# schematic.net
KiCad netlist of a schematic drawn in EAGLE
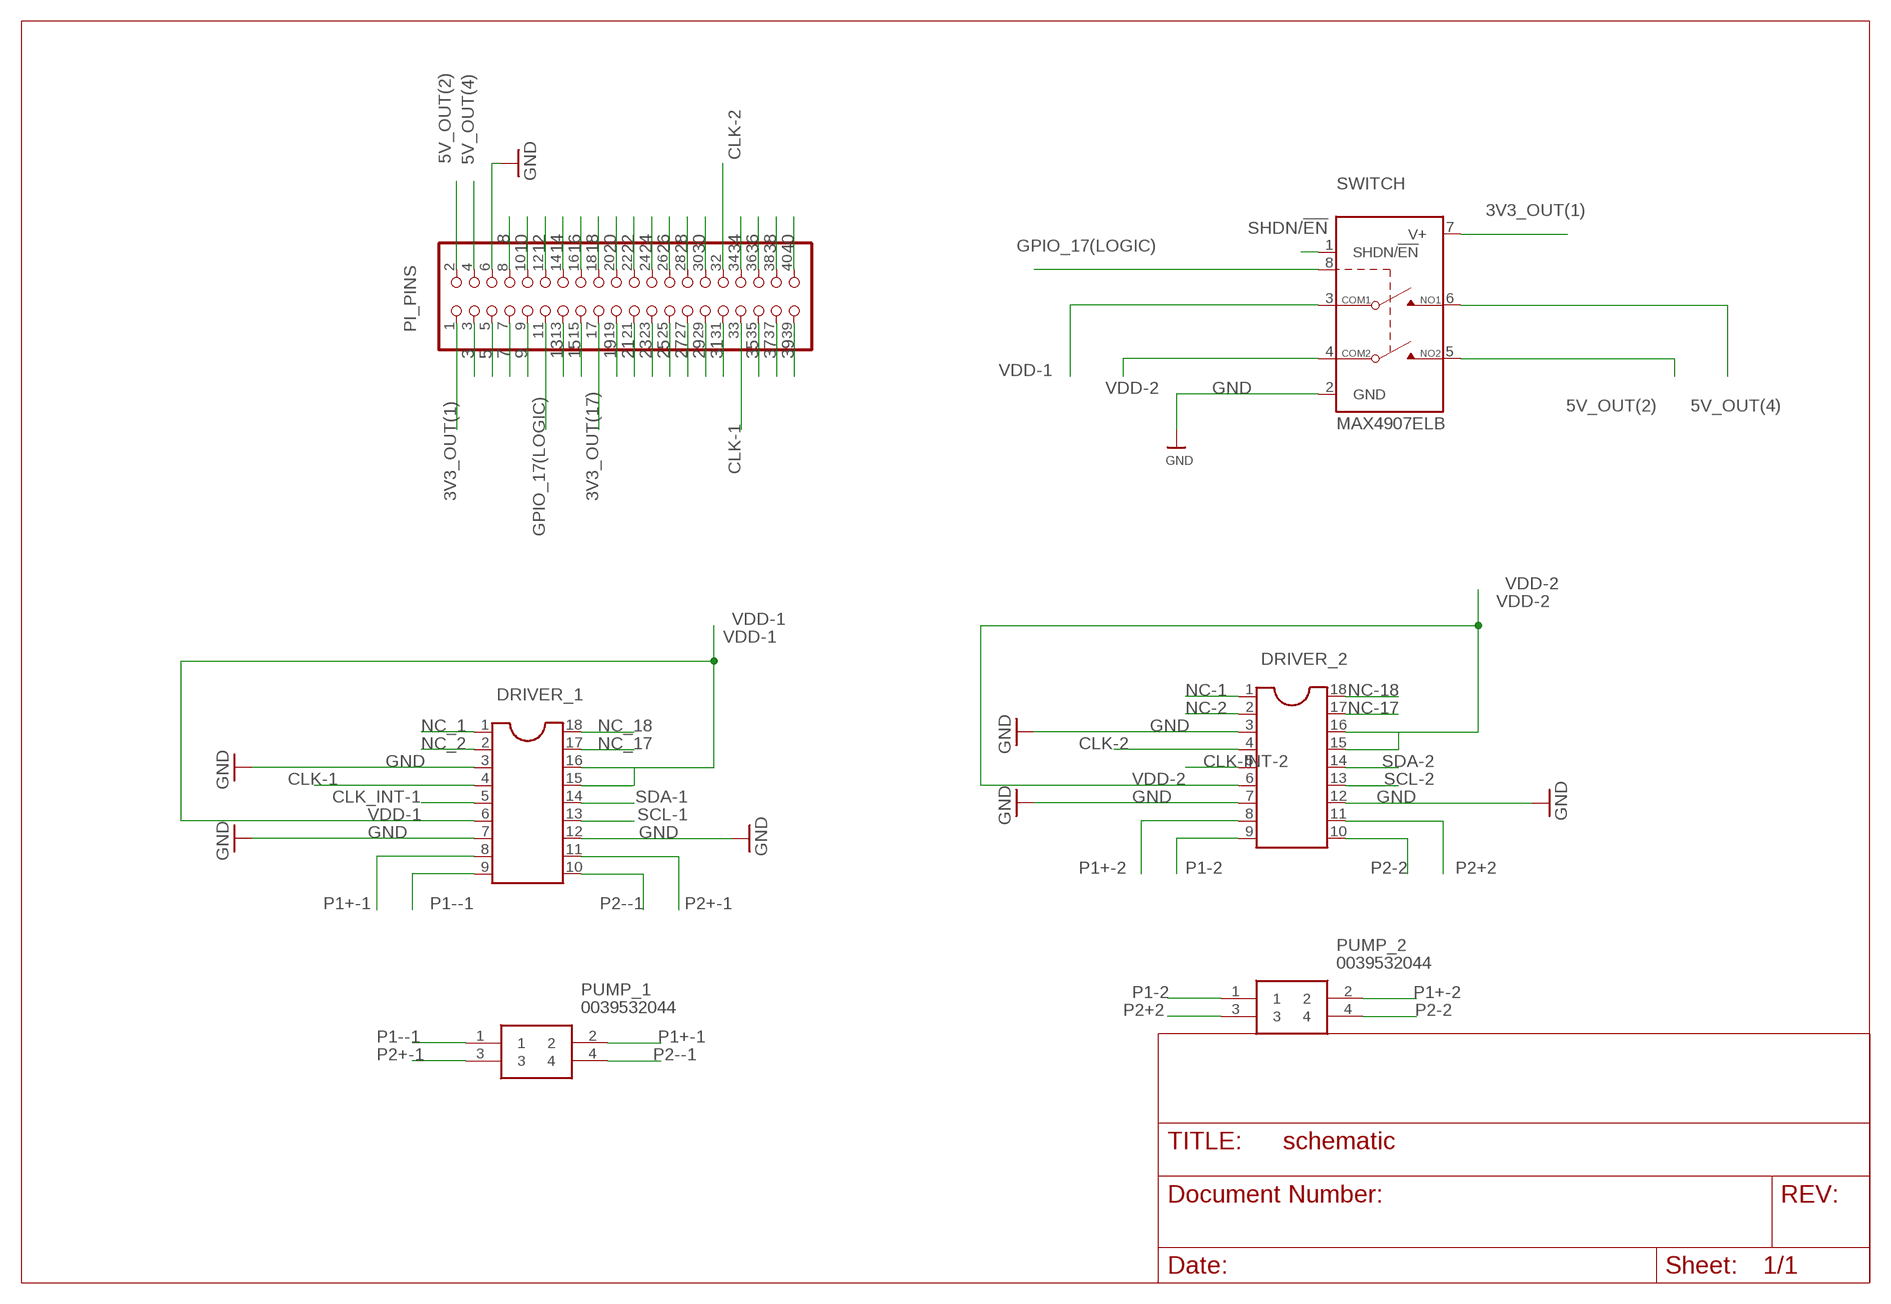
[diagram p0: schematic, sheet 1]

(export (version "E")
  (design (tool "Eeschema 10.0.6"))
  (components
    (comp (ref "DRIVER_1")
      (value "DIL18")
      (footprint "eagle-import:DIL18")
      (libsource (lib "eagle-import") (part "DIL18"))
    )
    (comp (ref "DRIVER_2")
      (value "DIL18")
      (footprint "eagle-import:DIL18")
      (libsource (lib "eagle-import") (part "DIL18"))
    )
    (comp (ref "PI_PINS")
      (value "PINHD-2X20")
      (footprint "eagle-import:2X20")
      (libsource (lib "eagle-import") (part "PINHD-2X20"))
    )
    (comp (ref "PUMP_1")
      (value "0039532044")
      (footprint "eagle-import:0039532044")
      (libsource (lib "eagle-import") (part "0039532044"))
    )
    (comp (ref "PUMP_2")
      (value "0039532044")
      (footprint "eagle-import:0039532044")
      (libsource (lib "eagle-import") (part "0039532044"))
    )
    (comp (ref "SWITCH")
      (value "MAX4907ELB")
      (footprint "eagle-import:UDFN8")
      (libsource (lib "eagle-import") (part "MAX4907ELB"))
    )
  )
  (nets
    (net (code "1") (name "/3") (class "Default")
      (node (ref "PI_PINS") (pin "3") (pinfunction "3_3") (pintype "passive"))
    )
    (net (code "2") (name "/3V3_OUT(1)") (class "Default")
      (node (ref "PI_PINS") (pin "1") (pinfunction "1_1") (pintype "passive"))
      (node (ref "SWITCH") (pin "7") (pinfunction "V+_7") (pintype "input"))
    )
    (net (code "3") (name "/3V3_OUT(17)") (class "Default")
      (node (ref "PI_PINS") (pin "17") (pinfunction "17_17") (pintype "passive"))
    )
    (net (code "4") (name "/5") (class "Default")
      (node (ref "PI_PINS") (pin "5") (pinfunction "5_5") (pintype "passive"))
    )
    (net (code "5") (name "/5V_OUT(2)") (class "Default")
      (node (ref "PI_PINS") (pin "2") (pinfunction "2_2") (pintype "passive"))
      (node (ref "SWITCH") (pin "5") (pinfunction "NO2_5") (pintype "bidirectional"))
    )
    (net (code "6") (name "/5V_OUT(4)") (class "Default")
      (node (ref "PI_PINS") (pin "4") (pinfunction "4_4") (pintype "passive"))
      (node (ref "SWITCH") (pin "6") (pinfunction "NO1_6") (pintype "bidirectional"))
    )
    (net (code "7") (name "/7") (class "Default")
      (node (ref "PI_PINS") (pin "7") (pinfunction "7_7") (pintype "passive"))
    )
    (net (code "8") (name "/8") (class "Default")
      (node (ref "PI_PINS") (pin "8") (pinfunction "8_8") (pintype "passive"))
    )
    (net (code "9") (name "/9") (class "Default")
      (node (ref "PI_PINS") (pin "9") (pinfunction "9_9") (pintype "passive"))
    )
    (net (code "10") (name "/10") (class "Default")
      (node (ref "PI_PINS") (pin "10") (pinfunction "10_10") (pintype "passive"))
    )
    (net (code "11") (name "/12") (class "Default")
      (node (ref "PI_PINS") (pin "12") (pinfunction "12_12") (pintype "passive"))
    )
    (net (code "12") (name "/13") (class "Default")
      (node (ref "PI_PINS") (pin "13") (pinfunction "13_13") (pintype "passive"))
    )
    (net (code "13") (name "/14") (class "Default")
      (node (ref "PI_PINS") (pin "14") (pinfunction "14_14") (pintype "passive"))
    )
    (net (code "14") (name "/15") (class "Default")
      (node (ref "PI_PINS") (pin "15") (pinfunction "15_15") (pintype "passive"))
    )
    (net (code "15") (name "/16") (class "Default")
      (node (ref "PI_PINS") (pin "16") (pinfunction "16_16") (pintype "passive"))
    )
    (net (code "16") (name "/18") (class "Default")
      (node (ref "PI_PINS") (pin "18") (pinfunction "18_18") (pintype "passive"))
    )
    (net (code "17") (name "/19") (class "Default")
      (node (ref "PI_PINS") (pin "19") (pinfunction "19_19") (pintype "passive"))
    )
    (net (code "18") (name "/20") (class "Default")
      (node (ref "PI_PINS") (pin "20") (pinfunction "20_20") (pintype "passive"))
    )
    (net (code "19") (name "/21") (class "Default")
      (node (ref "PI_PINS") (pin "21") (pinfunction "21_21") (pintype "passive"))
    )
    (net (code "20") (name "/22") (class "Default")
      (node (ref "PI_PINS") (pin "22") (pinfunction "22_22") (pintype "passive"))
    )
    (net (code "21") (name "/23") (class "Default")
      (node (ref "PI_PINS") (pin "23") (pinfunction "23_23") (pintype "passive"))
    )
    (net (code "22") (name "/24") (class "Default")
      (node (ref "PI_PINS") (pin "24") (pinfunction "24_24") (pintype "passive"))
    )
    (net (code "23") (name "/25") (class "Default")
      (node (ref "PI_PINS") (pin "25") (pinfunction "25_25") (pintype "passive"))
    )
    (net (code "24") (name "/26") (class "Default")
      (node (ref "PI_PINS") (pin "26") (pinfunction "26_26") (pintype "passive"))
    )
    (net (code "25") (name "/27") (class "Default")
      (node (ref "PI_PINS") (pin "27") (pinfunction "27_27") (pintype "passive"))
    )
    (net (code "26") (name "/28") (class "Default")
      (node (ref "PI_PINS") (pin "28") (pinfunction "28_28") (pintype "passive"))
    )
    (net (code "27") (name "/29") (class "Default")
      (node (ref "PI_PINS") (pin "29") (pinfunction "29_29") (pintype "passive"))
    )
    (net (code "28") (name "/30") (class "Default")
      (node (ref "PI_PINS") (pin "30") (pinfunction "30_30") (pintype "passive"))
    )
    (net (code "29") (name "/31") (class "Default")
      (node (ref "PI_PINS") (pin "31") (pinfunction "31_31") (pintype "passive"))
    )
    (net (code "30") (name "/34") (class "Default")
      (node (ref "PI_PINS") (pin "34") (pinfunction "34_34") (pintype "passive"))
    )
    (net (code "31") (name "/35") (class "Default")
      (node (ref "PI_PINS") (pin "35") (pinfunction "35_35") (pintype "passive"))
    )
    (net (code "32") (name "/36") (class "Default")
      (node (ref "PI_PINS") (pin "36") (pinfunction "36_36") (pintype "passive"))
    )
    (net (code "33") (name "/37") (class "Default")
      (node (ref "PI_PINS") (pin "37") (pinfunction "37_37") (pintype "passive"))
    )
    (net (code "34") (name "/38") (class "Default")
      (node (ref "PI_PINS") (pin "38") (pinfunction "38_38") (pintype "passive"))
    )
    (net (code "35") (name "/39") (class "Default")
      (node (ref "PI_PINS") (pin "39") (pinfunction "39_39") (pintype "passive"))
    )
    (net (code "36") (name "/40") (class "Default")
      (node (ref "PI_PINS") (pin "40") (pinfunction "40_40") (pintype "passive"))
    )
    (net (code "37") (name "/CLK-1") (class "Default")
      (node (ref "DRIVER_1") (pin "4") (pinfunction "4_4") (pintype "passive"))
      (node (ref "PI_PINS") (pin "33") (pinfunction "33_33") (pintype "passive"))
    )
    (net (code "38") (name "/CLK-2") (class "Default")
      (node (ref "DRIVER_2") (pin "4") (pinfunction "4_4") (pintype "passive"))
      (node (ref "PI_PINS") (pin "32") (pinfunction "32_32") (pintype "passive"))
    )
    (net (code "39") (name "/CLK-INT-2") (class "Default")
      (node (ref "DRIVER_2") (pin "5") (pinfunction "5_5") (pintype "passive"))
    )
    (net (code "40") (name "/CLK_INT-1") (class "Default")
      (node (ref "DRIVER_1") (pin "5") (pinfunction "5_5") (pintype "passive"))
    )
    (net (code "41") (name "/GPIO_17(LOGIC)") (class "Default")
      (node (ref "PI_PINS") (pin "11") (pinfunction "11_11") (pintype "passive"))
      (node (ref "SWITCH") (pin "8") (pinfunction "IN_8") (pintype "input"))
    )
    (net (code "42") (name "/NC-1") (class "Default")
      (node (ref "DRIVER_2") (pin "1") (pinfunction "1_1") (pintype "passive"))
    )
    (net (code "43") (name "/NC-2") (class "Default")
      (node (ref "DRIVER_2") (pin "2") (pinfunction "2_2") (pintype "passive"))
    )
    (net (code "44") (name "/NC-17") (class "Default")
      (node (ref "DRIVER_2") (pin "17") (pinfunction "17_17") (pintype "passive"))
    )
    (net (code "45") (name "/NC-18") (class "Default")
      (node (ref "DRIVER_2") (pin "18") (pinfunction "18_18") (pintype "passive"))
    )
    (net (code "46") (name "/NC_1") (class "Default")
      (node (ref "DRIVER_1") (pin "1") (pinfunction "1_1") (pintype "passive"))
    )
    (net (code "47") (name "/NC_2") (class "Default")
      (node (ref "DRIVER_1") (pin "2") (pinfunction "2_2") (pintype "passive"))
    )
    (net (code "48") (name "/NC_17") (class "Default")
      (node (ref "DRIVER_1") (pin "17") (pinfunction "17_17") (pintype "passive"))
    )
    (net (code "49") (name "/NC_18") (class "Default")
      (node (ref "DRIVER_1") (pin "18") (pinfunction "18_18") (pintype "passive"))
    )
    (net (code "50") (name "/P1+-1") (class "Default")
      (node (ref "DRIVER_1") (pin "8") (pinfunction "8_8") (pintype "passive"))
      (node (ref "PUMP_1") (pin "2") (pinfunction "2_2") (pintype "bidirectional"))
    )
    (net (code "51") (name "/P1+-2") (class "Default")
      (node (ref "DRIVER_2") (pin "8") (pinfunction "8_8") (pintype "passive"))
      (node (ref "PUMP_2") (pin "2") (pinfunction "2_2") (pintype "bidirectional"))
    )
    (net (code "52") (name "/P1--1") (class "Default")
      (node (ref "DRIVER_1") (pin "9") (pinfunction "9_9") (pintype "passive"))
      (node (ref "PUMP_1") (pin "1") (pinfunction "1_1") (pintype "bidirectional"))
    )
    (net (code "53") (name "/P1-2") (class "Default")
      (node (ref "DRIVER_2") (pin "9") (pinfunction "9_9") (pintype "passive"))
      (node (ref "PUMP_2") (pin "1") (pinfunction "1_1") (pintype "bidirectional"))
    )
    (net (code "54") (name "/P2+-1") (class "Default")
      (node (ref "DRIVER_1") (pin "11") (pinfunction "11_11") (pintype "passive"))
      (node (ref "PUMP_1") (pin "3") (pinfunction "3_3") (pintype "bidirectional"))
    )
    (net (code "55") (name "/P2+2") (class "Default")
      (node (ref "DRIVER_2") (pin "11") (pinfunction "11_11") (pintype "passive"))
      (node (ref "PUMP_2") (pin "3") (pinfunction "3_3") (pintype "bidirectional"))
    )
    (net (code "56") (name "/P2--1") (class "Default")
      (node (ref "DRIVER_1") (pin "10") (pinfunction "10_10") (pintype "passive"))
      (node (ref "PUMP_1") (pin "4") (pinfunction "4_4") (pintype "bidirectional"))
    )
    (net (code "57") (name "/P2-2") (class "Default")
      (node (ref "DRIVER_2") (pin "10") (pinfunction "10_10") (pintype "passive"))
      (node (ref "PUMP_2") (pin "4") (pinfunction "4_4") (pintype "bidirectional"))
    )
    (net (code "58") (name "/SCL-1") (class "Default")
      (node (ref "DRIVER_1") (pin "13") (pinfunction "13_13") (pintype "passive"))
    )
    (net (code "59") (name "/SCL-2") (class "Default")
      (node (ref "DRIVER_2") (pin "13") (pinfunction "13_13") (pintype "passive"))
    )
    (net (code "60") (name "/SDA-1") (class "Default")
      (node (ref "DRIVER_1") (pin "14") (pinfunction "14_14") (pintype "passive"))
    )
    (net (code "61") (name "/SDA-2") (class "Default")
      (node (ref "DRIVER_2") (pin "14") (pinfunction "14_14") (pintype "passive"))
    )
    (net (code "62") (name "/SHDN{slash}~{EN}") (class "Default")
      (node (ref "SWITCH") (pin "1") (pinfunction "SHDN/~{EN}_1") (pintype "input"))
    )
    (net (code "63") (name "/VDD-1") (class "Default")
      (node (ref "DRIVER_1") (pin "15") (pinfunction "15_15") (pintype "passive"))
      (node (ref "DRIVER_1") (pin "16") (pinfunction "16_16") (pintype "passive"))
      (node (ref "DRIVER_1") (pin "6") (pinfunction "6_6") (pintype "passive"))
      (node (ref "SWITCH") (pin "3") (pinfunction "COM1_3") (pintype "bidirectional"))
    )
    (net (code "64") (name "/VDD-2") (class "Default")
      (node (ref "DRIVER_2") (pin "15") (pinfunction "15_15") (pintype "passive"))
      (node (ref "DRIVER_2") (pin "16") (pinfunction "16_16") (pintype "passive"))
      (node (ref "DRIVER_2") (pin "6") (pinfunction "6_6") (pintype "passive"))
      (node (ref "SWITCH") (pin "4") (pinfunction "COM2_4") (pintype "bidirectional"))
    )
    (net (code "65") (name "GND") (class "Default")
      (node (ref "DRIVER_1") (pin "12") (pinfunction "12_12") (pintype "passive"))
      (node (ref "DRIVER_1") (pin "3") (pinfunction "3_3") (pintype "passive"))
      (node (ref "DRIVER_1") (pin "7") (pinfunction "7_7") (pintype "passive"))
      (node (ref "DRIVER_2") (pin "12") (pinfunction "12_12") (pintype "passive"))
      (node (ref "DRIVER_2") (pin "3") (pinfunction "3_3") (pintype "passive"))
      (node (ref "DRIVER_2") (pin "7") (pinfunction "7_7") (pintype "passive"))
      (node (ref "PI_PINS") (pin "6") (pinfunction "6_6") (pintype "passive"))
      (node (ref "SWITCH") (pin "2") (pinfunction "GND_2") (pintype "power_in"))
    )
  )
)
